# SampleProject.net
KiCad netlist of a schematic drawn in Altium Designer
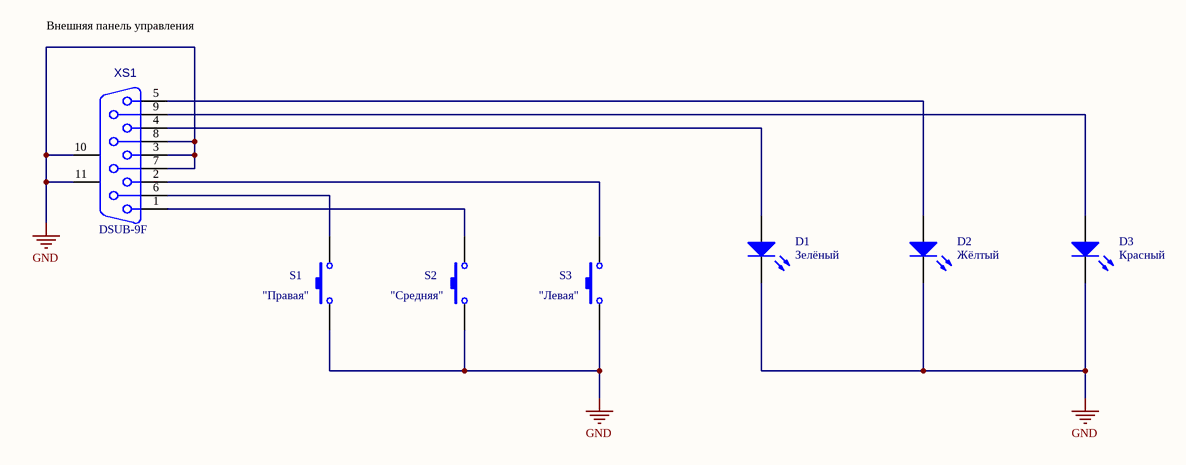
[diagram p0: SampleProject.SchDoc]

(export (version "E")
  (design (tool "Eeschema 10.0.6"))
  (components
    (comp (ref "D1")
      (value "Зелёный")
      (footprint "CeleronLib_THD:LED_5MM_GREEN_1C-2A")
      (description "Typical LED")
      (fields (field (name "VOLTAGE") "3V") (field (name "Comment") "Светодиод  выводной 5mm  Зелёный"))
      (libsource (lib "CeleronLib") (part "LED"))
    )
    (comp (ref "D2")
      (value "Жёлтый")
      (footprint "CeleronLib_THD:LED_5MM_YELLOW_1C-2A")
      (description "Typical LED")
      (fields (field (name "VOLTAGE") "3V") (field (name "Comment") "Светодиод  выводной 5mm  Жёлтый"))
      (libsource (lib "CeleronLib") (part "LED"))
    )
    (comp (ref "D3")
      (value "Красный")
      (footprint "CeleronLib_THD:LED_5MM_RED_1C-2A")
      (description "Typical LED")
      (fields (field (name "VOLTAGE") "3V") (field (name "Comment") "Светодиод  выводной 5mm  Красный"))
      (libsource (lib "CeleronLib") (part "LED"))
    )
    (comp (ref "S1")
      (value "Кнопка TACT 12x12-5.0")
      (footprint "CeleronLib_THD:TACT 12x12-5.0 DIP")
      (description "Push-Button (TACT)")
      (fields (field (name "NAME") "\"Права \""))
      (libsource (lib "CeleronLib") (part "SW-PB"))
    )
    (comp (ref "S2")
      (value "Кнопка TACT 12x12-5.0")
      (footprint "CeleronLib_THD:TACT 12x12-5.0 DIP")
      (description "Push-Button (TACT)")
      (fields (field (name "NAME") "\"Средн  \""))
      (libsource (lib "CeleronLib") (part "SW-PB"))
    )
    (comp (ref "S3")
      (value "Кнопка TACT 12x12-5.0")
      (footprint "CeleronLib_THD:TACT 12x12-5.0 DIP")
      (description "Push-Button (TACT)")
      (fields (field (name "NAME") "\"Лева \""))
      (libsource (lib "CeleronLib") (part "SW-PB"))
    )
    (comp (ref "XS1")
      (value "Разъём DSUB-9F")
      (footprint "CeleronLib_Connect:DSUB-9F")
      (description "DSub-9 pin female 90*")
      (fields (field (name "NAME") "Внешн   панель управлени ") (field (name "DEVICE") "DSUB-9F"))
      (libsource (lib "CeleronLib_Connect") (part "DSUB-9F"))
    )
  )
  (nets
    (net (code "1") (name "GND") (class "Default")
      (node (ref "D1") (pin "1") (pinfunction "C_1") (pintype "passive"))
      (node (ref "D2") (pin "1") (pinfunction "C_1") (pintype "passive"))
      (node (ref "D3") (pin "1") (pinfunction "C_1") (pintype "passive"))
      (node (ref "S1") (pin "1") (pinfunction "1_1") (pintype "passive"))
      (node (ref "S2") (pin "1") (pinfunction "1_1") (pintype "passive"))
      (node (ref "S3") (pin "1") (pinfunction "1_1") (pintype "passive"))
      (node (ref "XS1") (pin "10") (pinfunction "MH1_10") (pintype "passive"))
      (node (ref "XS1") (pin "11") (pinfunction "MH2_11") (pintype "passive"))
      (node (ref "XS1") (pin "3") (pinfunction "3_3") (pintype "passive"))
      (node (ref "XS1") (pin "7") (pinfunction "7_7") (pintype "passive"))
      (node (ref "XS1") (pin "8") (pinfunction "8_8") (pintype "passive"))
    )
    (net (code "2") (name "Net-(D1-A)") (class "Default")
      (node (ref "D1") (pin "2") (pinfunction "A_2") (pintype "passive"))
      (node (ref "XS1") (pin "4") (pinfunction "4_4") (pintype "passive"))
    )
    (net (code "3") (name "Net-(D2-A)") (class "Default")
      (node (ref "D2") (pin "2") (pinfunction "A_2") (pintype "passive"))
      (node (ref "XS1") (pin "5") (pinfunction "5_5") (pintype "passive"))
    )
    (net (code "4") (name "Net-(D3-A)") (class "Default")
      (node (ref "D3") (pin "2") (pinfunction "A_2") (pintype "passive"))
      (node (ref "XS1") (pin "9") (pinfunction "9_9") (pintype "passive"))
    )
    (net (code "5") (name "Net-(S1-Pad2)") (class "Default")
      (node (ref "S1") (pin "2") (pinfunction "2_2") (pintype "passive"))
      (node (ref "XS1") (pin "6") (pinfunction "6_6") (pintype "passive"))
    )
    (net (code "6") (name "Net-(S2-Pad2)") (class "Default")
      (node (ref "S2") (pin "2") (pinfunction "2_2") (pintype "passive"))
      (node (ref "XS1") (pin "1") (pinfunction "1_1") (pintype "passive"))
    )
    (net (code "7") (name "Net-(S3-Pad2)") (class "Default")
      (node (ref "S3") (pin "2") (pinfunction "2_2") (pintype "passive"))
      (node (ref "XS1") (pin "2") (pinfunction "2_2") (pintype "passive"))
    )
  )
)
